# LoRa_Shield.net
KiCad netlist of a schematic drawn in EAGLE
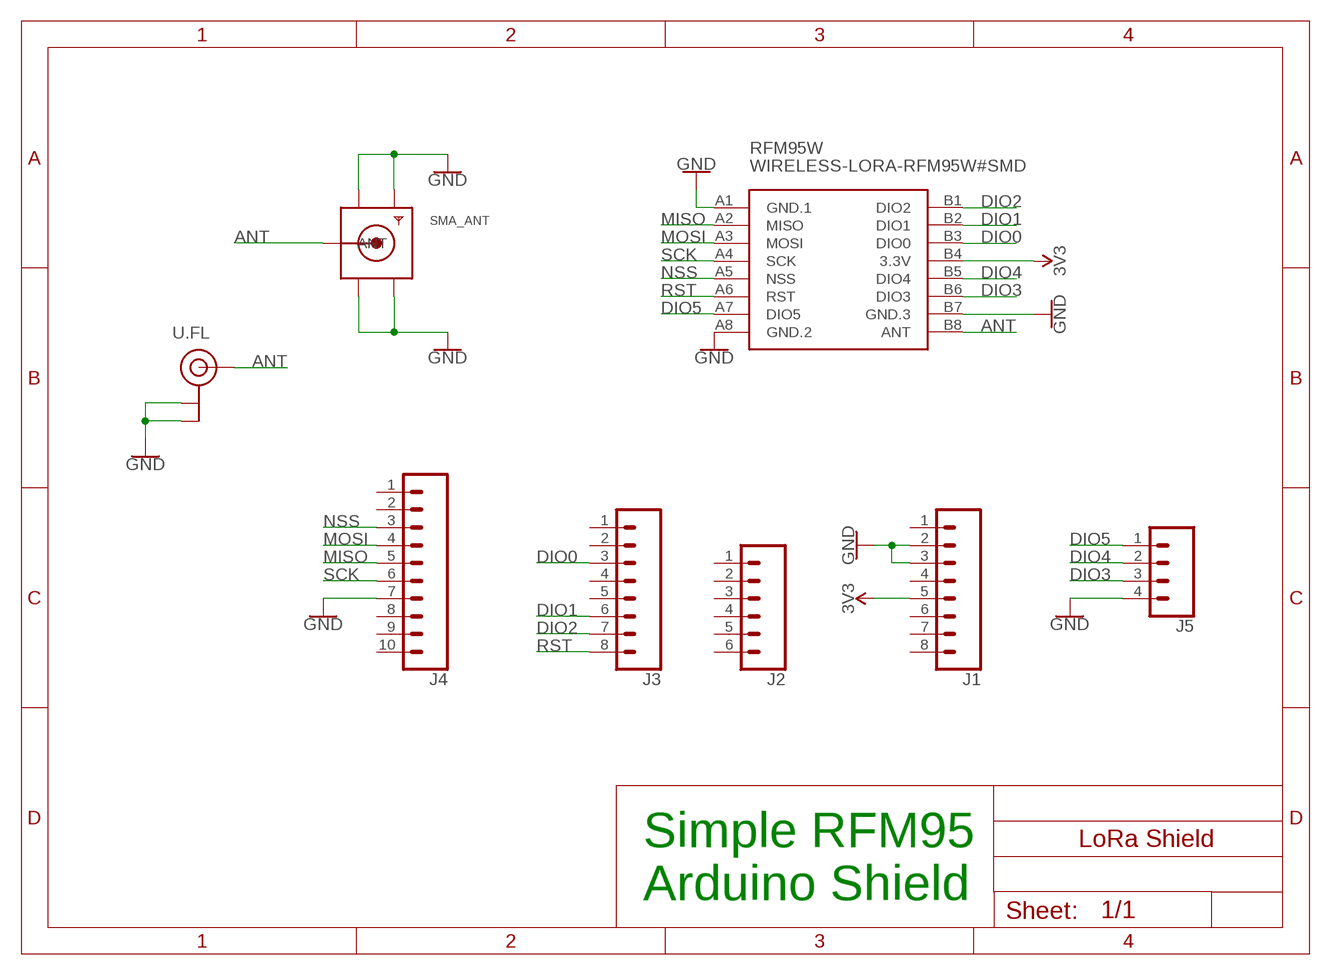
[diagram p0: schematic, sheet 1]

(export (version "E")
  (design (tool "Eeschema 10.0.6"))
  (components
    (comp (ref "J1")
      (value "CONN_08\"")
      (footprint "eagle-import:1X08")
      (libsource (lib "eagle-import") (part "CONN_08{dblquote}"))
    )
    (comp (ref "J2")
      (value "CONN_06SILK_FEMALE_PTH")
      (footprint "eagle-import:1X06")
      (libsource (lib "eagle-import") (part "CONN_06SILK_FEMALE_PTH"))
    )
    (comp (ref "J3")
      (value "CONN_08\"")
      (footprint "eagle-import:1X08")
      (libsource (lib "eagle-import") (part "CONN_08{dblquote}"))
    )
    (comp (ref "J4")
      (value "CONN_10\"")
      (footprint "eagle-import:1X10")
      (libsource (lib "eagle-import") (part "CONN_10{dblquote}"))
    )
    (comp (ref "J5")
      (value "CONN_04PTH")
      (footprint "eagle-import:1X04")
      (libsource (lib "eagle-import") (part "CONN_04PTH"))
    )
    (comp (ref "RFM95W")
      (value "WIRELESS-LORA-RFM95W#SMD")
      (footprint "eagle-import:WIRELESS-LORA-RFM95W#SMD")
      (libsource (lib "eagle-import") (part "WIRELESS-LORA-RFM95W#SMD"))
    )
    (comp (ref "SMA_ANT")
      (value "SMACONNECTOR")
      (footprint "eagle-import:SMA90_DIP")
      (libsource (lib "eagle-import") (part "SMACONNECTOR"))
    )
    (comp (ref "U.FL")
      (value "U.FL")
      (footprint "eagle-import:U.FL")
      (libsource (lib "eagle-import") (part "U.FL"))
    )
  )
  (nets
    (net (code "1") (name "/ANT") (class "Default")
      (node (ref "RFM95W") (pin "B8") (pinfunction "ANT_B8") (pintype "passive"))
      (node (ref "SMA_ANT") (pin "ANTENNA") (pinfunction "ANT_ANTENNA") (pintype "bidirectional"))
      (node (ref "U.FL") (pin "FEED") (pinfunction "SIGNAL_FEED") (pintype "bidirectional"))
    )
    (net (code "2") (name "/DIO0") (class "Default")
      (node (ref "J3") (pin "3") (pinfunction "3_3") (pintype "passive"))
      (node (ref "RFM95W") (pin "B3") (pinfunction "DIO0_B3") (pintype "bidirectional"))
    )
    (net (code "3") (name "/DIO1") (class "Default")
      (node (ref "J3") (pin "6") (pinfunction "6_6") (pintype "passive"))
      (node (ref "RFM95W") (pin "B2") (pinfunction "DIO1_B2") (pintype "bidirectional"))
    )
    (net (code "4") (name "/DIO2") (class "Default")
      (node (ref "J3") (pin "7") (pinfunction "7_7") (pintype "passive"))
      (node (ref "RFM95W") (pin "B1") (pinfunction "DIO2_B1") (pintype "bidirectional"))
    )
    (net (code "5") (name "/DIO3") (class "Default")
      (node (ref "J5") (pin "3") (pinfunction "3_3") (pintype "passive"))
      (node (ref "RFM95W") (pin "B6") (pinfunction "DIO3_B6") (pintype "bidirectional"))
    )
    (net (code "6") (name "/DIO4") (class "Default")
      (node (ref "J5") (pin "2") (pinfunction "2_2") (pintype "passive"))
      (node (ref "RFM95W") (pin "B5") (pinfunction "DIO4_B5") (pintype "bidirectional"))
    )
    (net (code "7") (name "/DIO5") (class "Default")
      (node (ref "J5") (pin "1") (pinfunction "1_1") (pintype "passive"))
      (node (ref "RFM95W") (pin "A7") (pinfunction "DIO5_A7") (pintype "bidirectional"))
    )
    (net (code "8") (name "/MISO") (class "Default")
      (node (ref "J4") (pin "5") (pinfunction "5_5") (pintype "passive"))
      (node (ref "RFM95W") (pin "A2") (pinfunction "MISO_A2") (pintype "bidirectional"))
    )
    (net (code "9") (name "/MOSI") (class "Default")
      (node (ref "J4") (pin "4") (pinfunction "4_4") (pintype "passive"))
      (node (ref "RFM95W") (pin "A3") (pinfunction "MOSI_A3") (pintype "bidirectional"))
    )
    (net (code "10") (name "/NSS") (class "Default")
      (node (ref "J4") (pin "3") (pinfunction "3_3") (pintype "passive"))
      (node (ref "RFM95W") (pin "A5") (pinfunction "NSS_A5") (pintype "bidirectional"))
    )
    (net (code "11") (name "/RST") (class "Default")
      (node (ref "J3") (pin "8") (pinfunction "8_8") (pintype "passive"))
      (node (ref "RFM95W") (pin "A6") (pinfunction "RST_A6") (pintype "bidirectional"))
    )
    (net (code "12") (name "/SCK") (class "Default")
      (node (ref "J4") (pin "6") (pinfunction "6_6") (pintype "passive"))
      (node (ref "RFM95W") (pin "A4") (pinfunction "SCK_A4") (pintype "bidirectional"))
    )
    (net (code "13") (name "3V3") (class "Default")
      (node (ref "J1") (pin "5") (pinfunction "5_5") (pintype "passive"))
      (node (ref "RFM95W") (pin "B4") (pinfunction "3.3V_B4") (pintype "power_in"))
    )
    (net (code "14") (name "GND") (class "Default")
      (node (ref "J1") (pin "2") (pinfunction "2_2") (pintype "passive"))
      (node (ref "J1") (pin "3") (pinfunction "3_3") (pintype "passive"))
      (node (ref "J4") (pin "7") (pinfunction "7_7") (pintype "passive"))
      (node (ref "J5") (pin "4") (pinfunction "4_4") (pintype "passive"))
      (node (ref "RFM95W") (pin "A1") (pinfunction "GND.1_A1") (pintype "power_in"))
      (node (ref "RFM95W") (pin "A8") (pinfunction "GND.2_A8") (pintype "power_in"))
      (node (ref "RFM95W") (pin "B7") (pinfunction "GND.3_B7") (pintype "power_in"))
      (node (ref "SMA_ANT") (pin "GND1") (pinfunction "GND1_GND1") (pintype "power_in"))
      (node (ref "SMA_ANT") (pin "GND2") (pinfunction "GND2_GND2") (pintype "power_in"))
      (node (ref "SMA_ANT") (pin "GND3") (pinfunction "GND3_GND3") (pintype "power_in"))
      (node (ref "SMA_ANT") (pin "GND4") (pinfunction "GND4_GND4") (pintype "power_in"))
      (node (ref "U.FL") (pin "1") (pinfunction "GND_1") (pintype "bidirectional"))
      (node (ref "U.FL") (pin "2") (pinfunction "GND_2") (pintype "bidirectional"))
    )
    (net (code "15") (name "unconnected-(J1-Pad1)") (class "Default")
      (node (ref "J1") (pin "1") (pinfunction "1_1") (pintype "passive"))
    )
    (net (code "16") (name "unconnected-(J1-Pad4)") (class "Default")
      (node (ref "J1") (pin "4") (pinfunction "4_4") (pintype "passive"))
    )
    (net (code "17") (name "unconnected-(J1-Pad6)") (class "Default")
      (node (ref "J1") (pin "6") (pinfunction "6_6") (pintype "passive"))
    )
    (net (code "18") (name "unconnected-(J1-Pad7)") (class "Default")
      (node (ref "J1") (pin "7") (pinfunction "7_7") (pintype "passive"))
    )
    (net (code "19") (name "unconnected-(J1-Pad8)") (class "Default")
      (node (ref "J1") (pin "8") (pinfunction "8_8") (pintype "passive"))
    )
    (net (code "20") (name "unconnected-(J2-Pad1)") (class "Default")
      (node (ref "J2") (pin "1") (pinfunction "1_1") (pintype "passive"))
    )
    (net (code "21") (name "unconnected-(J2-Pad2)") (class "Default")
      (node (ref "J2") (pin "2") (pinfunction "2_2") (pintype "passive"))
    )
    (net (code "22") (name "unconnected-(J2-Pad3)") (class "Default")
      (node (ref "J2") (pin "3") (pinfunction "3_3") (pintype "passive"))
    )
    (net (code "23") (name "unconnected-(J2-Pad4)") (class "Default")
      (node (ref "J2") (pin "4") (pinfunction "4_4") (pintype "passive"))
    )
    (net (code "24") (name "unconnected-(J2-Pad5)") (class "Default")
      (node (ref "J2") (pin "5") (pinfunction "5_5") (pintype "passive"))
    )
    (net (code "25") (name "unconnected-(J2-Pad6)") (class "Default")
      (node (ref "J2") (pin "6") (pinfunction "6_6") (pintype "passive"))
    )
    (net (code "26") (name "unconnected-(J3-Pad1)") (class "Default")
      (node (ref "J3") (pin "1") (pinfunction "1_1") (pintype "passive"))
    )
    (net (code "27") (name "unconnected-(J3-Pad2)") (class "Default")
      (node (ref "J3") (pin "2") (pinfunction "2_2") (pintype "passive"))
    )
    (net (code "28") (name "unconnected-(J3-Pad4)") (class "Default")
      (node (ref "J3") (pin "4") (pinfunction "4_4") (pintype "passive"))
    )
    (net (code "29") (name "unconnected-(J3-Pad5)") (class "Default")
      (node (ref "J3") (pin "5") (pinfunction "5_5") (pintype "passive"))
    )
    (net (code "30") (name "unconnected-(J4-Pad1)") (class "Default")
      (node (ref "J4") (pin "1") (pinfunction "1_1") (pintype "passive"))
    )
    (net (code "31") (name "unconnected-(J4-Pad2)") (class "Default")
      (node (ref "J4") (pin "2") (pinfunction "2_2") (pintype "passive"))
    )
    (net (code "32") (name "unconnected-(J4-Pad8)") (class "Default")
      (node (ref "J4") (pin "8") (pinfunction "8_8") (pintype "passive"))
    )
    (net (code "33") (name "unconnected-(J4-Pad9)") (class "Default")
      (node (ref "J4") (pin "9") (pinfunction "9_9") (pintype "passive"))
    )
    (net (code "34") (name "unconnected-(J4-Pad10)") (class "Default")
      (node (ref "J4") (pin "10") (pinfunction "10_10") (pintype "passive"))
    )
  )
)
